# QUTMS-TSAL-S02.net
KiCad netlist of a schematic drawn in Altium Designer
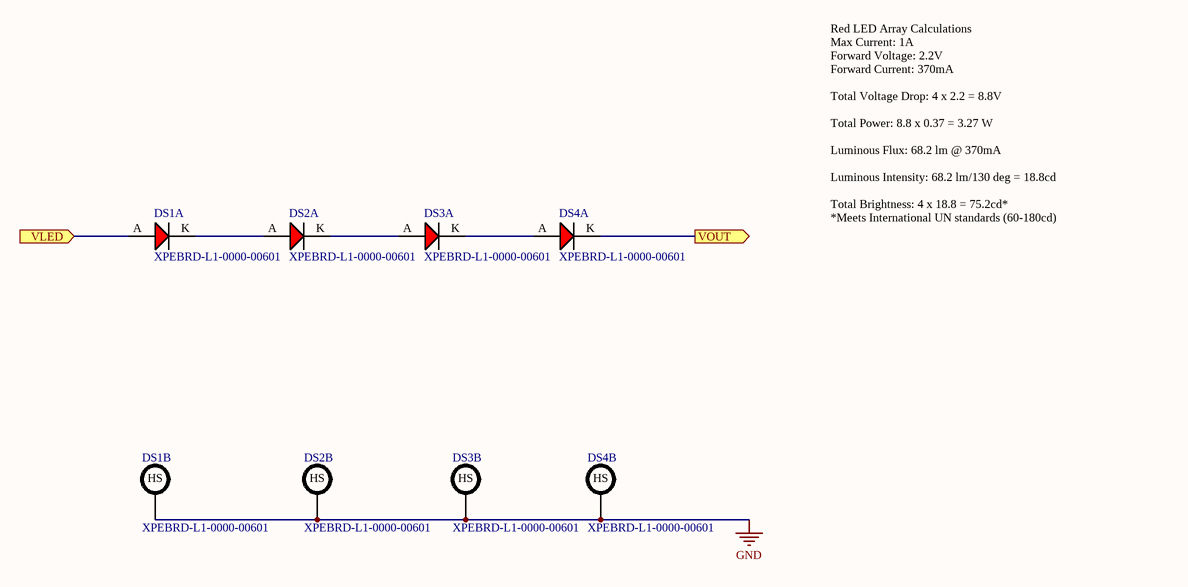
[diagram p0: QUTMS-TSAL-S02.SchDoc]

(export (version "E")
  (design (tool "Eeschema 10.0.6"))
  (components
    (comp (ref "DS1")
      (value "XPEBRD-L1-0000-00601")
      (footprint "Cree XLamp XP-E2")
      (description "LED, Cree XLamp XP-E2 Series, Red, 630 nm, 130 °, 62 lm, 1 A")
      (libsource (lib "QUTMS_LEDLibrary") (part "XPEBRD-L1-0000-00601"))
    )
    (comp (ref "DS2")
      (value "XPEBRD-L1-0000-00601")
      (footprint "Cree XLamp XP-E2")
      (description "LED, Cree XLamp XP-E2 Series, Red, 630 nm, 130 °, 62 lm, 1 A")
      (libsource (lib "QUTMS_LEDLibrary") (part "XPEBRD-L1-0000-00601"))
    )
    (comp (ref "DS3")
      (value "XPEBRD-L1-0000-00601")
      (footprint "Cree XLamp XP-E2")
      (description "LED, Cree XLamp XP-E2 Series, Red, 630 nm, 130 °, 62 lm, 1 A")
      (libsource (lib "QUTMS_LEDLibrary") (part "XPEBRD-L1-0000-00601"))
    )
    (comp (ref "DS4")
      (value "XPEBRD-L1-0000-00601")
      (footprint "Cree XLamp XP-E2")
      (description "LED, Cree XLamp XP-E2 Series, Red, 630 nm, 130 °, 62 lm, 1 A")
      (libsource (lib "QUTMS_LEDLibrary") (part "XPEBRD-L1-0000-00601"))
    )
  )
  (nets
    (net (code "1") (name "/VLED") (class "Default")
      (node (ref "DS1") (pin "A") (pinfunction "A_A") (pintype "passive"))
    )
    (net (code "2") (name "/VOUT") (class "Default")
      (node (ref "DS4") (pin "K") (pinfunction "K_K") (pintype "passive"))
    )
    (net (code "3") (name "GND") (class "Default")
      (node (ref "DS1") (pin "HS") (pinfunction "HS_HS") (pintype "passive"))
      (node (ref "DS2") (pin "HS") (pinfunction "HS_HS") (pintype "passive"))
      (node (ref "DS3") (pin "HS") (pinfunction "HS_HS") (pintype "passive"))
      (node (ref "DS4") (pin "HS") (pinfunction "HS_HS") (pintype "passive"))
    )
    (net (code "4") (name "Net-(DS1-PadK)") (class "Default")
      (node (ref "DS1") (pin "K") (pinfunction "K_K") (pintype "passive"))
      (node (ref "DS2") (pin "A") (pinfunction "A_A") (pintype "passive"))
    )
    (net (code "5") (name "Net-(DS2-PadK)") (class "Default")
      (node (ref "DS2") (pin "K") (pinfunction "K_K") (pintype "passive"))
      (node (ref "DS3") (pin "A") (pinfunction "A_A") (pintype "passive"))
    )
    (net (code "6") (name "Net-(DS3-PadK)") (class "Default")
      (node (ref "DS3") (pin "K") (pinfunction "K_K") (pintype "passive"))
      (node (ref "DS4") (pin "A") (pinfunction "A_A") (pintype "passive"))
    )
  )
)
